# bbf-thonkjacks.net
KiCad netlist of a schematic drawn in EAGLE
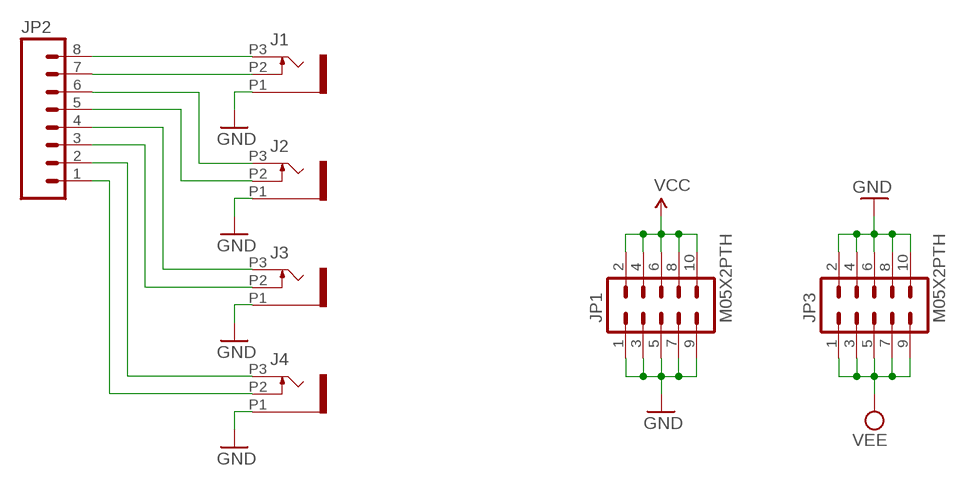
[diagram p0: schematic, sheet 1]

(export (version "E")
  (design (tool "Eeschema 10.0.6"))
  (components
    (comp (ref "J1")
      (value "OG-PJ301_PJ301_THONKICONN4")
      (footprint "eagle-import:OG-PJ301_WQP_PJ_301M4")
      (libsource (lib "eagle-import") (part "OG-PJ301_PJ301_THONKICONN4"))
    )
    (comp (ref "J2")
      (value "OG-PJ301_PJ301_THONKICONN4")
      (footprint "eagle-import:OG-PJ301_WQP_PJ_301M4")
      (libsource (lib "eagle-import") (part "OG-PJ301_PJ301_THONKICONN4"))
    )
    (comp (ref "J3")
      (value "OG-PJ301_PJ301_THONKICONN4")
      (footprint "eagle-import:OG-PJ301_WQP_PJ_301M4")
      (libsource (lib "eagle-import") (part "OG-PJ301_PJ301_THONKICONN4"))
    )
    (comp (ref "J4")
      (value "OG-PJ301_PJ301_THONKICONN4")
      (footprint "eagle-import:OG-PJ301_WQP_PJ_301M4")
      (libsource (lib "eagle-import") (part "OG-PJ301_PJ301_THONKICONN4"))
    )
    (comp (ref "JP1")
      (value "M05X2PTH")
      (footprint "eagle-import:AVR_ICSP")
      (libsource (lib "eagle-import") (part "M05X2PTH"))
    )
    (comp (ref "JP2")
      (value "M08")
      (footprint "eagle-import:1X08")
      (libsource (lib "eagle-import") (part "M08"))
    )
    (comp (ref "JP3")
      (value "M05X2PTH")
      (footprint "eagle-import:AVR_ICSP")
      (libsource (lib "eagle-import") (part "M05X2PTH"))
    )
  )
  (nets
    (net (code "1") (name "GND") (class "Default")
      (node (ref "J1") (pin "P1") (pinfunction "1_P1") (pintype "passive"))
      (node (ref "J2") (pin "P1") (pinfunction "1_P1") (pintype "passive"))
      (node (ref "J3") (pin "P1") (pinfunction "1_P1") (pintype "passive"))
      (node (ref "J4") (pin "P1") (pinfunction "1_P1") (pintype "passive"))
      (node (ref "JP1") (pin "1") (pinfunction "1_1") (pintype "passive"))
      (node (ref "JP1") (pin "3") (pinfunction "3_3") (pintype "passive"))
      (node (ref "JP1") (pin "5") (pinfunction "5_5") (pintype "passive"))
      (node (ref "JP1") (pin "7") (pinfunction "7_7") (pintype "passive"))
      (node (ref "JP1") (pin "9") (pinfunction "9_9") (pintype "passive"))
      (node (ref "JP3") (pin "10") (pinfunction "10_10") (pintype "passive"))
      (node (ref "JP3") (pin "2") (pinfunction "2_2") (pintype "passive"))
      (node (ref "JP3") (pin "4") (pinfunction "4_4") (pintype "passive"))
      (node (ref "JP3") (pin "6") (pinfunction "6_6") (pintype "passive"))
      (node (ref "JP3") (pin "8") (pinfunction "8_8") (pintype "passive"))
    )
    (net (code "2") (name "Net-(J1-2)") (class "Default")
      (node (ref "J1") (pin "P2") (pinfunction "2_P2") (pintype "passive"))
      (node (ref "JP2") (pin "7") (pinfunction "7_7") (pintype "passive"))
    )
    (net (code "3") (name "Net-(J1-3)") (class "Default")
      (node (ref "J1") (pin "P3") (pinfunction "3_P3") (pintype "passive"))
      (node (ref "JP2") (pin "8") (pinfunction "8_8") (pintype "passive"))
    )
    (net (code "4") (name "Net-(J2-2)") (class "Default")
      (node (ref "J2") (pin "P2") (pinfunction "2_P2") (pintype "passive"))
      (node (ref "JP2") (pin "5") (pinfunction "5_5") (pintype "passive"))
    )
    (net (code "5") (name "Net-(J2-3)") (class "Default")
      (node (ref "J2") (pin "P3") (pinfunction "3_P3") (pintype "passive"))
      (node (ref "JP2") (pin "6") (pinfunction "6_6") (pintype "passive"))
    )
    (net (code "6") (name "Net-(J3-2)") (class "Default")
      (node (ref "J3") (pin "P2") (pinfunction "2_P2") (pintype "passive"))
      (node (ref "JP2") (pin "3") (pinfunction "3_3") (pintype "passive"))
    )
    (net (code "7") (name "Net-(J3-3)") (class "Default")
      (node (ref "J3") (pin "P3") (pinfunction "3_P3") (pintype "passive"))
      (node (ref "JP2") (pin "4") (pinfunction "4_4") (pintype "passive"))
    )
    (net (code "8") (name "Net-(J4-2)") (class "Default")
      (node (ref "J4") (pin "P2") (pinfunction "2_P2") (pintype "passive"))
      (node (ref "JP2") (pin "1") (pinfunction "1_1") (pintype "passive"))
    )
    (net (code "9") (name "Net-(J4-3)") (class "Default")
      (node (ref "J4") (pin "P3") (pinfunction "3_P3") (pintype "passive"))
      (node (ref "JP2") (pin "2") (pinfunction "2_2") (pintype "passive"))
    )
    (net (code "10") (name "VCC") (class "Default")
      (node (ref "JP1") (pin "10") (pinfunction "10_10") (pintype "passive"))
      (node (ref "JP1") (pin "2") (pinfunction "2_2") (pintype "passive"))
      (node (ref "JP1") (pin "4") (pinfunction "4_4") (pintype "passive"))
      (node (ref "JP1") (pin "6") (pinfunction "6_6") (pintype "passive"))
      (node (ref "JP1") (pin "8") (pinfunction "8_8") (pintype "passive"))
    )
    (net (code "11") (name "VEE") (class "Default")
      (node (ref "JP3") (pin "1") (pinfunction "1_1") (pintype "passive"))
      (node (ref "JP3") (pin "3") (pinfunction "3_3") (pintype "passive"))
      (node (ref "JP3") (pin "5") (pinfunction "5_5") (pintype "passive"))
      (node (ref "JP3") (pin "7") (pinfunction "7_7") (pintype "passive"))
      (node (ref "JP3") (pin "9") (pinfunction "9_9") (pintype "passive"))
    )
  )
)
